# controller.net
KiCad netlist of a schematic drawn in EAGLE
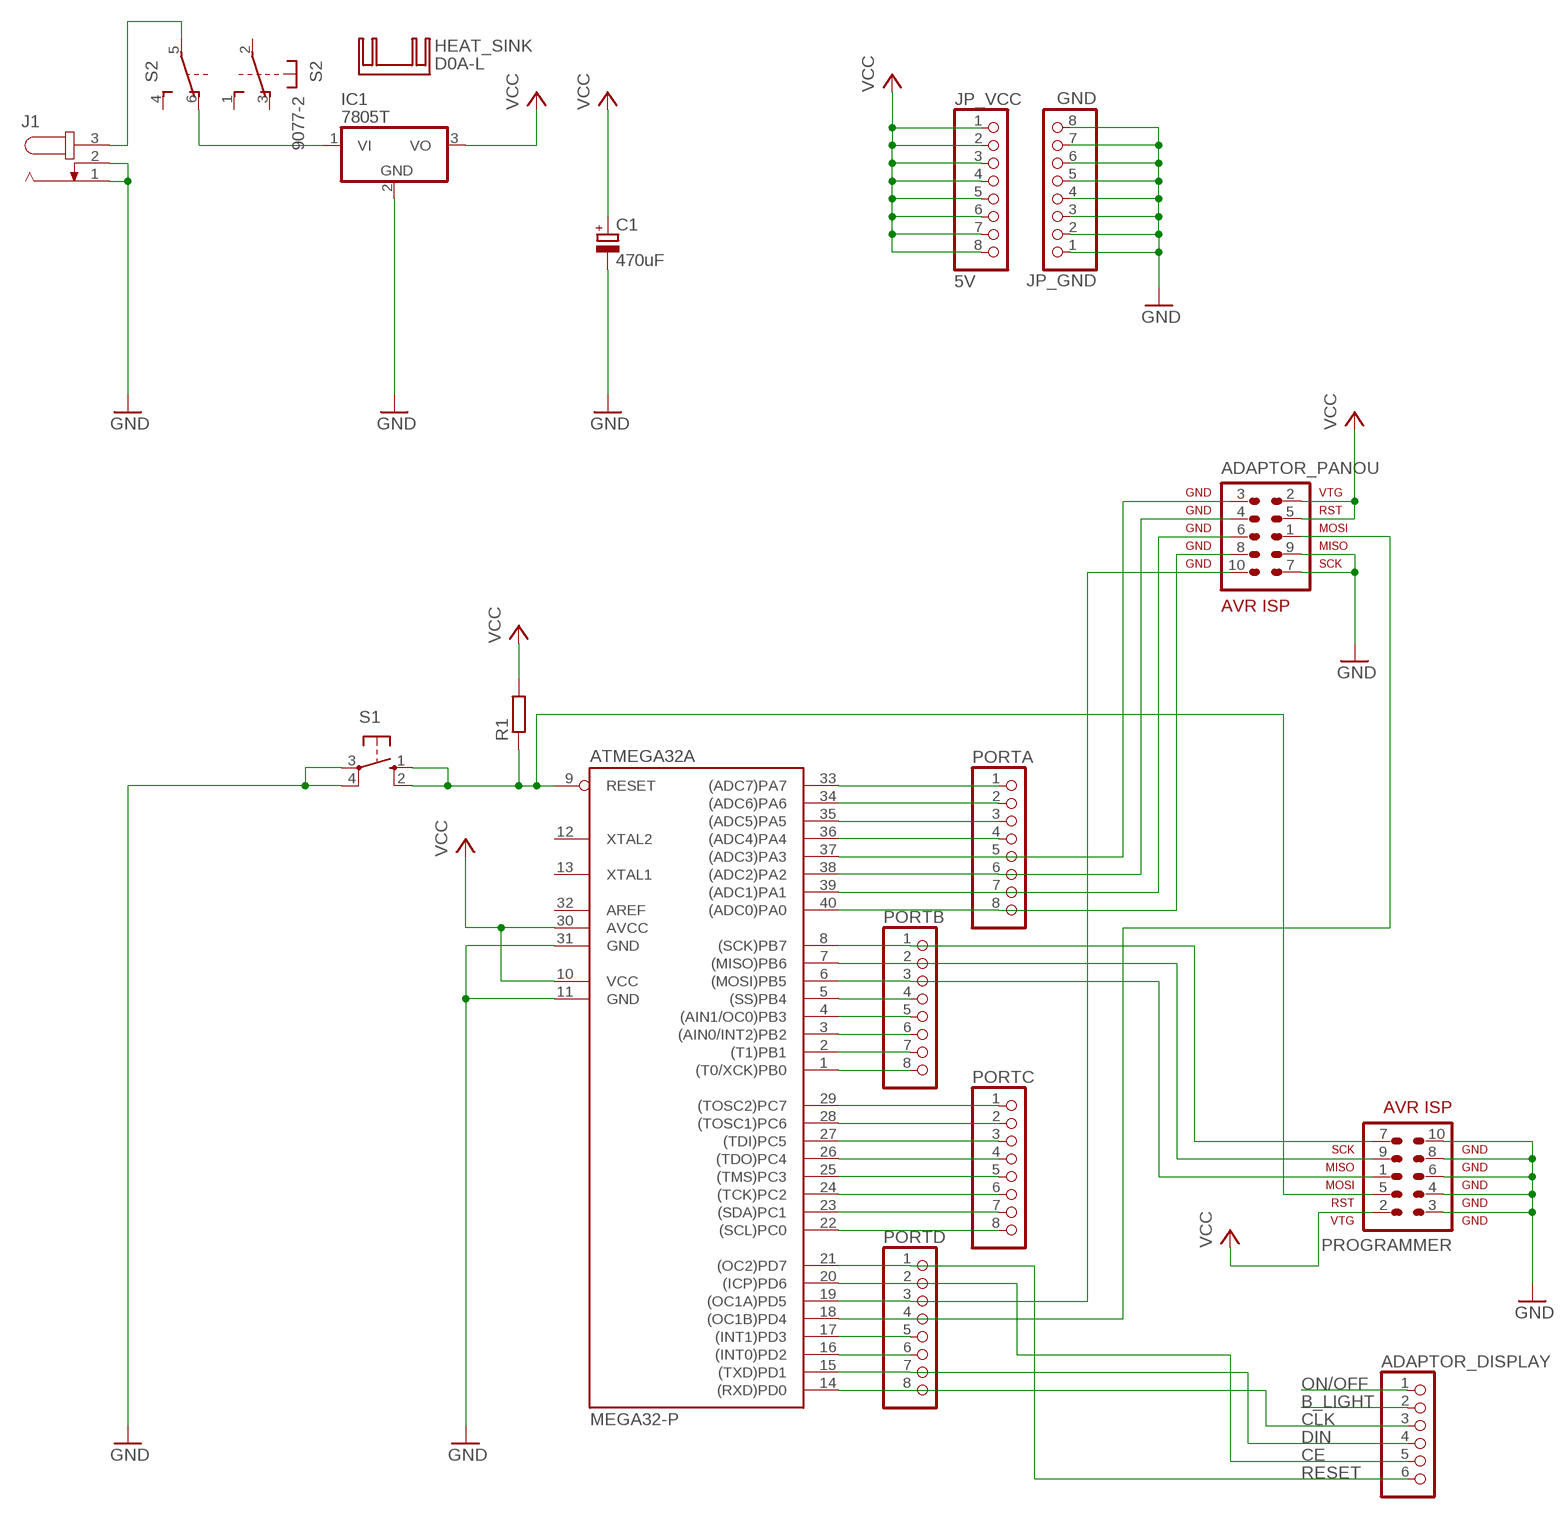
[diagram p0: schematic, sheet 1]

(export (version "E")
  (design (tool "Eeschema 10.0.6"))
  (components
    (comp (ref "ADAPTOR_DISPLAY")
      (value "PINHD-1X6")
      (footprint "eagle-import:1X06")
      (libsource (lib "eagle-import") (part "PINHD-1X6"))
    )
    (comp (ref "ADAPTOR_PANOU")
      (value "AVR-ISP-10")
      (footprint "eagle-import:AVR-ISP-10")
      (libsource (lib "eagle-import") (part "AVR-ISP-10"))
    )
    (comp (ref "ATMEGA32A")
      (value "MEGA32-P")
      (footprint "eagle-import:DIL40")
      (fields (field (name "MPN") "ATMEGA32-16PU"))
      (libsource (lib "eagle-import") (part "MEGA32-P"))
    )
    (comp (ref "C1")
      (value "470uF")
      (footprint "eagle-import:E3,5-8")
      (libsource (lib "eagle-import") (part "CPOL-EUE3.5-8"))
    )
    (comp (ref "HEAT_SINK")
      (value "D0A-L")
      (footprint "eagle-import:D02A-L")
      (libsource (lib "eagle-import") (part "D0A-L"))
    )
    (comp (ref "IC1")
      (value "7805T")
      (footprint "eagle-import:TO220H")
      (libsource (lib "eagle-import") (part "78T05"))
    )
    (comp (ref "J1")
      (value "JACK-PLUG0")
      (footprint "eagle-import:SPC4077")
      (libsource (lib "eagle-import") (part "JACK-PLUG0"))
    )
    (comp (ref "JP_GND")
      (value "GND")
      (footprint "eagle-import:1X08")
      (libsource (lib "eagle-import") (part "PINHD-1X8"))
    )
    (comp (ref "JP_VCC")
      (value "5V")
      (footprint "eagle-import:1X08")
      (libsource (lib "eagle-import") (part "PINHD-1X8"))
    )
    (comp (ref "PORTA")
      (value "PINHD-1X8")
      (footprint "eagle-import:1X08")
      (libsource (lib "eagle-import") (part "PINHD-1X8"))
    )
    (comp (ref "PORTB")
      (value "PINHD-1X8")
      (footprint "eagle-import:1X08")
      (libsource (lib "eagle-import") (part "PINHD-1X8"))
    )
    (comp (ref "PORTC")
      (value "PINHD-1X8")
      (footprint "eagle-import:1X08")
      (libsource (lib "eagle-import") (part "PINHD-1X8"))
    )
    (comp (ref "PORTD")
      (value "PINHD-1X8")
      (footprint "eagle-import:1X08")
      (libsource (lib "eagle-import") (part "PINHD-1X8"))
    )
    (comp (ref "PROGRAMMER")
      (value "AVR-ISP-10")
      (footprint "eagle-import:AVR-ISP-10")
      (libsource (lib "eagle-import") (part "AVR-ISP-10"))
    )
    (comp (ref "R1")
      (value "R-EU_0207/10")
      (footprint "eagle-import:0207_10")
      (libsource (lib "eagle-import") (part "R-EU_0207/10"))
    )
    (comp (ref "S1")
      (value "10-XX")
      (footprint "eagle-import:B3F-10XX")
      (fields (field (name "MPN") "B3F-1000"))
      (libsource (lib "eagle-import") (part "10-XX"))
    )
    (comp (ref "S2")
      (value "9077-2")
      (footprint "eagle-import:9077-2")
      (libsource (lib "eagle-import") (part "9077-2"))
    )
  )
  (nets
    (net (code "1") (name "/B_LIGHT") (class "Default")
      (node (ref "ADAPTOR_DISPLAY") (pin "2") (pinfunction "2_2") (pintype "passive"))
    )
    (net (code "2") (name "/CE") (class "Default")
      (node (ref "ADAPTOR_DISPLAY") (pin "5") (pinfunction "5_5") (pintype "passive"))
      (node (ref "ATMEGA32A") (pin "20") (pinfunction "(ICP)PD6_20") (pintype "bidirectional"))
      (node (ref "PORTD") (pin "2") (pinfunction "2_2") (pintype "passive"))
    )
    (net (code "3") (name "/CLK") (class "Default")
      (node (ref "ADAPTOR_DISPLAY") (pin "3") (pinfunction "3_3") (pintype "passive"))
      (node (ref "ATMEGA32A") (pin "14") (pinfunction "(RXD)PD0_14") (pintype "bidirectional"))
      (node (ref "PORTD") (pin "8") (pinfunction "8_8") (pintype "passive"))
    )
    (net (code "4") (name "/DIN") (class "Default")
      (node (ref "ADAPTOR_DISPLAY") (pin "4") (pinfunction "4_4") (pintype "passive"))
      (node (ref "ATMEGA32A") (pin "15") (pinfunction "(TXD)PD1_15") (pintype "bidirectional"))
      (node (ref "PORTD") (pin "7") (pinfunction "7_7") (pintype "passive"))
    )
    (net (code "5") (name "/ON{slash}OFF") (class "Default")
      (node (ref "ADAPTOR_DISPLAY") (pin "1") (pinfunction "1_1") (pintype "passive"))
    )
    (net (code "6") (name "/RESET") (class "Default")
      (node (ref "ADAPTOR_DISPLAY") (pin "6") (pinfunction "6_6") (pintype "passive"))
      (node (ref "ATMEGA32A") (pin "21") (pinfunction "(OC2)PD7_21") (pintype "bidirectional"))
      (node (ref "PORTD") (pin "1") (pinfunction "1_1") (pintype "passive"))
    )
    (net (code "7") (name "GND") (class "Default")
      (node (ref "ADAPTOR_PANOU") (pin "7") (pinfunction "7_7") (pintype "passive"))
      (node (ref "ADAPTOR_PANOU") (pin "9") (pinfunction "9_9") (pintype "passive"))
      (node (ref "ATMEGA32A") (pin "11") (pinfunction "GND_11") (pintype "power_in"))
      (node (ref "ATMEGA32A") (pin "31") (pinfunction "GND_31") (pintype "power_in"))
      (node (ref "C1") (pin "-") (pinfunction "-_-") (pintype "passive"))
      (node (ref "IC1") (pin "2") (pinfunction "GND_2") (pintype "passive"))
      (node (ref "J1") (pin "1") (pinfunction "1_1") (pintype "passive"))
      (node (ref "J1") (pin "2") (pinfunction "2_2") (pintype "passive"))
      (node (ref "JP_GND") (pin "1") (pinfunction "1_1") (pintype "passive"))
      (node (ref "JP_GND") (pin "2") (pinfunction "2_2") (pintype "passive"))
      (node (ref "JP_GND") (pin "3") (pinfunction "3_3") (pintype "passive"))
      (node (ref "JP_GND") (pin "4") (pinfunction "4_4") (pintype "passive"))
      (node (ref "JP_GND") (pin "5") (pinfunction "5_5") (pintype "passive"))
      (node (ref "JP_GND") (pin "6") (pinfunction "6_6") (pintype "passive"))
      (node (ref "JP_GND") (pin "7") (pinfunction "7_7") (pintype "passive"))
      (node (ref "JP_GND") (pin "8") (pinfunction "8_8") (pintype "passive"))
      (node (ref "PROGRAMMER") (pin "10") (pinfunction "10_10") (pintype "passive"))
      (node (ref "PROGRAMMER") (pin "3") (pinfunction "3_3") (pintype "passive"))
      (node (ref "PROGRAMMER") (pin "4") (pinfunction "4_4") (pintype "passive"))
      (node (ref "PROGRAMMER") (pin "6") (pinfunction "6_6") (pintype "passive"))
      (node (ref "PROGRAMMER") (pin "8") (pinfunction "8_8") (pintype "passive"))
      (node (ref "S1") (pin "3") (pinfunction "P_3") (pintype "passive"))
      (node (ref "S1") (pin "4") (pinfunction "P1_4") (pintype "passive"))
    )
    (net (code "8") (name "Net-(ATMEGA32A-(ADC0)PA0)") (class "Default")
      (node (ref "ADAPTOR_PANOU") (pin "8") (pinfunction "8_8") (pintype "passive"))
      (node (ref "ATMEGA32A") (pin "40") (pinfunction "(ADC0)PA0_40") (pintype "bidirectional"))
      (node (ref "PORTA") (pin "8") (pinfunction "8_8") (pintype "passive"))
    )
    (net (code "9") (name "Net-(ATMEGA32A-(ADC1)PA1)") (class "Default")
      (node (ref "ADAPTOR_PANOU") (pin "6") (pinfunction "6_6") (pintype "passive"))
      (node (ref "ATMEGA32A") (pin "39") (pinfunction "(ADC1)PA1_39") (pintype "bidirectional"))
      (node (ref "PORTA") (pin "7") (pinfunction "7_7") (pintype "passive"))
    )
    (net (code "10") (name "Net-(ATMEGA32A-(ADC2)PA2)") (class "Default")
      (node (ref "ADAPTOR_PANOU") (pin "4") (pinfunction "4_4") (pintype "passive"))
      (node (ref "ATMEGA32A") (pin "38") (pinfunction "(ADC2)PA2_38") (pintype "bidirectional"))
      (node (ref "PORTA") (pin "6") (pinfunction "6_6") (pintype "passive"))
    )
    (net (code "11") (name "Net-(ATMEGA32A-(ADC3)PA3)") (class "Default")
      (node (ref "ADAPTOR_PANOU") (pin "3") (pinfunction "3_3") (pintype "passive"))
      (node (ref "ATMEGA32A") (pin "37") (pinfunction "(ADC3)PA3_37") (pintype "bidirectional"))
      (node (ref "PORTA") (pin "5") (pinfunction "5_5") (pintype "passive"))
    )
    (net (code "12") (name "Net-(ATMEGA32A-(ADC4)PA4)") (class "Default")
      (node (ref "ATMEGA32A") (pin "36") (pinfunction "(ADC4)PA4_36") (pintype "bidirectional"))
      (node (ref "PORTA") (pin "4") (pinfunction "4_4") (pintype "passive"))
    )
    (net (code "13") (name "Net-(ATMEGA32A-(ADC5)PA5)") (class "Default")
      (node (ref "ATMEGA32A") (pin "35") (pinfunction "(ADC5)PA5_35") (pintype "bidirectional"))
      (node (ref "PORTA") (pin "3") (pinfunction "3_3") (pintype "passive"))
    )
    (net (code "14") (name "Net-(ATMEGA32A-(ADC6)PA6)") (class "Default")
      (node (ref "ATMEGA32A") (pin "34") (pinfunction "(ADC6)PA6_34") (pintype "bidirectional"))
      (node (ref "PORTA") (pin "2") (pinfunction "2_2") (pintype "passive"))
    )
    (net (code "15") (name "Net-(ATMEGA32A-(ADC7)PA7)") (class "Default")
      (node (ref "ATMEGA32A") (pin "33") (pinfunction "(ADC7)PA7_33") (pintype "bidirectional"))
      (node (ref "PORTA") (pin "1") (pinfunction "1_1") (pintype "passive"))
    )
    (net (code "16") (name "Net-(ATMEGA32A-(AIN0{slash}INT2)PB2)") (class "Default")
      (node (ref "ATMEGA32A") (pin "3") (pinfunction "(AIN0/INT2)PB2_3") (pintype "bidirectional"))
      (node (ref "PORTB") (pin "6") (pinfunction "6_6") (pintype "passive"))
    )
    (net (code "17") (name "Net-(ATMEGA32A-(AIN1{slash}OC0)PB3)") (class "Default")
      (node (ref "ATMEGA32A") (pin "4") (pinfunction "(AIN1/OC0)PB3_4") (pintype "bidirectional"))
      (node (ref "PORTB") (pin "5") (pinfunction "5_5") (pintype "passive"))
    )
    (net (code "18") (name "Net-(ATMEGA32A-(INT0)PD2)") (class "Default")
      (node (ref "ATMEGA32A") (pin "16") (pinfunction "(INT0)PD2_16") (pintype "bidirectional"))
      (node (ref "PORTD") (pin "6") (pinfunction "6_6") (pintype "passive"))
    )
    (net (code "19") (name "Net-(ATMEGA32A-(INT1)PD3)") (class "Default")
      (node (ref "ATMEGA32A") (pin "17") (pinfunction "(INT1)PD3_17") (pintype "bidirectional"))
      (node (ref "PORTD") (pin "5") (pinfunction "5_5") (pintype "passive"))
    )
    (net (code "20") (name "Net-(ATMEGA32A-(MISO)PB6)") (class "Default")
      (node (ref "ATMEGA32A") (pin "7") (pinfunction "(MISO)PB6_7") (pintype "bidirectional"))
      (node (ref "PORTB") (pin "2") (pinfunction "2_2") (pintype "passive"))
      (node (ref "PROGRAMMER") (pin "9") (pinfunction "9_9") (pintype "passive"))
    )
    (net (code "21") (name "Net-(ATMEGA32A-(MOSI)PB5)") (class "Default")
      (node (ref "ATMEGA32A") (pin "6") (pinfunction "(MOSI)PB5_6") (pintype "bidirectional"))
      (node (ref "PORTB") (pin "3") (pinfunction "3_3") (pintype "passive"))
      (node (ref "PROGRAMMER") (pin "1") (pinfunction "1_1") (pintype "passive"))
    )
    (net (code "22") (name "Net-(ATMEGA32A-(OC1A)PD5)") (class "Default")
      (node (ref "ADAPTOR_PANOU") (pin "10") (pinfunction "10_10") (pintype "passive"))
      (node (ref "ATMEGA32A") (pin "19") (pinfunction "(OC1A)PD5_19") (pintype "bidirectional"))
      (node (ref "PORTD") (pin "3") (pinfunction "3_3") (pintype "passive"))
    )
    (net (code "23") (name "Net-(ATMEGA32A-(OC1B)PD4)") (class "Default")
      (node (ref "ADAPTOR_PANOU") (pin "1") (pinfunction "1_1") (pintype "passive"))
      (node (ref "ATMEGA32A") (pin "18") (pinfunction "(OC1B)PD4_18") (pintype "bidirectional"))
      (node (ref "PORTD") (pin "4") (pinfunction "4_4") (pintype "passive"))
    )
    (net (code "24") (name "Net-(ATMEGA32A-(SCK)PB7)") (class "Default")
      (node (ref "ATMEGA32A") (pin "8") (pinfunction "(SCK)PB7_8") (pintype "bidirectional"))
      (node (ref "PORTB") (pin "1") (pinfunction "1_1") (pintype "passive"))
      (node (ref "PROGRAMMER") (pin "7") (pinfunction "7_7") (pintype "passive"))
    )
    (net (code "25") (name "Net-(ATMEGA32A-(SCL)PC0)") (class "Default")
      (node (ref "ATMEGA32A") (pin "22") (pinfunction "(SCL)PC0_22") (pintype "bidirectional"))
      (node (ref "PORTC") (pin "8") (pinfunction "8_8") (pintype "passive"))
    )
    (net (code "26") (name "Net-(ATMEGA32A-(SDA)PC1)") (class "Default")
      (node (ref "ATMEGA32A") (pin "23") (pinfunction "(SDA)PC1_23") (pintype "bidirectional"))
      (node (ref "PORTC") (pin "7") (pinfunction "7_7") (pintype "passive"))
    )
    (net (code "27") (name "Net-(ATMEGA32A-(SS)PB4)") (class "Default")
      (node (ref "ATMEGA32A") (pin "5") (pinfunction "(SS)PB4_5") (pintype "bidirectional"))
      (node (ref "PORTB") (pin "4") (pinfunction "4_4") (pintype "passive"))
    )
    (net (code "28") (name "Net-(ATMEGA32A-(T0{slash}XCK)PB0)") (class "Default")
      (node (ref "ATMEGA32A") (pin "1") (pinfunction "(T0/XCK)PB0_1") (pintype "bidirectional"))
      (node (ref "PORTB") (pin "8") (pinfunction "8_8") (pintype "passive"))
    )
    (net (code "29") (name "Net-(ATMEGA32A-(T1)PB1)") (class "Default")
      (node (ref "ATMEGA32A") (pin "2") (pinfunction "(T1)PB1_2") (pintype "bidirectional"))
      (node (ref "PORTB") (pin "7") (pinfunction "7_7") (pintype "passive"))
    )
    (net (code "30") (name "Net-(ATMEGA32A-(TCK)PC2)") (class "Default")
      (node (ref "ATMEGA32A") (pin "24") (pinfunction "(TCK)PC2_24") (pintype "bidirectional"))
      (node (ref "PORTC") (pin "6") (pinfunction "6_6") (pintype "passive"))
    )
    (net (code "31") (name "Net-(ATMEGA32A-(TDI)PC5)") (class "Default")
      (node (ref "ATMEGA32A") (pin "27") (pinfunction "(TDI)PC5_27") (pintype "bidirectional"))
      (node (ref "PORTC") (pin "3") (pinfunction "3_3") (pintype "passive"))
    )
    (net (code "32") (name "Net-(ATMEGA32A-(TDO)PC4)") (class "Default")
      (node (ref "ATMEGA32A") (pin "26") (pinfunction "(TDO)PC4_26") (pintype "bidirectional"))
      (node (ref "PORTC") (pin "4") (pinfunction "4_4") (pintype "passive"))
    )
    (net (code "33") (name "Net-(ATMEGA32A-(TMS)PC3)") (class "Default")
      (node (ref "ATMEGA32A") (pin "25") (pinfunction "(TMS)PC3_25") (pintype "bidirectional"))
      (node (ref "PORTC") (pin "5") (pinfunction "5_5") (pintype "passive"))
    )
    (net (code "34") (name "Net-(ATMEGA32A-(TOSC1)PC6)") (class "Default")
      (node (ref "ATMEGA32A") (pin "28") (pinfunction "(TOSC1)PC6_28") (pintype "bidirectional"))
      (node (ref "PORTC") (pin "2") (pinfunction "2_2") (pintype "passive"))
    )
    (net (code "35") (name "Net-(ATMEGA32A-(TOSC2)PC7)") (class "Default")
      (node (ref "ATMEGA32A") (pin "29") (pinfunction "(TOSC2)PC7_29") (pintype "bidirectional"))
      (node (ref "PORTC") (pin "1") (pinfunction "1_1") (pintype "passive"))
    )
    (net (code "36") (name "Net-(ATMEGA32A-RESET)") (class "Default")
      (node (ref "ATMEGA32A") (pin "9") (pinfunction "RESET_9") (pintype "input"))
      (node (ref "PROGRAMMER") (pin "5") (pinfunction "5_5") (pintype "passive"))
      (node (ref "R1") (pin "1") (pinfunction "1_1") (pintype "passive"))
      (node (ref "S1") (pin "1") (pinfunction "S_1") (pintype "passive"))
      (node (ref "S1") (pin "2") (pinfunction "S1_2") (pintype "passive"))
    )
    (net (code "37") (name "Net-(IC1-VI)") (class "Default")
      (node (ref "IC1") (pin "1") (pinfunction "VI_1") (pintype "input"))
      (node (ref "S2") (pin "6") (pinfunction "O_6") (pintype "passive"))
    )
    (net (code "38") (name "Net-(S2B-P)") (class "Default")
      (node (ref "J1") (pin "3") (pinfunction "3_3") (pintype "passive"))
      (node (ref "S2") (pin "5") (pinfunction "P_5") (pintype "passive"))
    )
    (net (code "39") (name "VCC") (class "Default")
      (node (ref "ADAPTOR_PANOU") (pin "2") (pinfunction "2_2") (pintype "passive"))
      (node (ref "ADAPTOR_PANOU") (pin "5") (pinfunction "5_5") (pintype "passive"))
      (node (ref "ATMEGA32A") (pin "10") (pinfunction "VCC_10") (pintype "power_in"))
      (node (ref "ATMEGA32A") (pin "30") (pinfunction "AVCC_30") (pintype "power_in"))
      (node (ref "C1") (pin "+") (pinfunction "+_+") (pintype "passive"))
      (node (ref "IC1") (pin "3") (pinfunction "VO_3") (pintype "passive"))
      (node (ref "JP_VCC") (pin "1") (pinfunction "1_1") (pintype "passive"))
      (node (ref "JP_VCC") (pin "2") (pinfunction "2_2") (pintype "passive"))
      (node (ref "JP_VCC") (pin "3") (pinfunction "3_3") (pintype "passive"))
      (node (ref "JP_VCC") (pin "4") (pinfunction "4_4") (pintype "passive"))
      (node (ref "JP_VCC") (pin "5") (pinfunction "5_5") (pintype "passive"))
      (node (ref "JP_VCC") (pin "6") (pinfunction "6_6") (pintype "passive"))
      (node (ref "JP_VCC") (pin "7") (pinfunction "7_7") (pintype "passive"))
      (node (ref "JP_VCC") (pin "8") (pinfunction "8_8") (pintype "passive"))
      (node (ref "PROGRAMMER") (pin "2") (pinfunction "2_2") (pintype "passive"))
      (node (ref "R1") (pin "2") (pinfunction "2_2") (pintype "passive"))
    )
    (net (code "40") (name "unconnected-(ATMEGA32A-AREF-Pad32)") (class "Default")
      (node (ref "ATMEGA32A") (pin "32") (pinfunction "AREF_32") (pintype "passive"))
    )
    (net (code "41") (name "unconnected-(ATMEGA32A-XTAL1-Pad13)") (class "Default")
      (node (ref "ATMEGA32A") (pin "13") (pinfunction "XTAL1_13") (pintype "bidirectional"))
    )
    (net (code "42") (name "unconnected-(ATMEGA32A-XTAL2-Pad12)") (class "Default")
      (node (ref "ATMEGA32A") (pin "12") (pinfunction "XTAL2_12") (pintype "bidirectional"))
    )
    (net (code "43") (name "unconnected-(S2A-O-Pad3)") (class "Default")
      (node (ref "S2") (pin "3") (pinfunction "O_3") (pintype "passive"))
    )
    (net (code "44") (name "unconnected-(S2A-P-Pad2)") (class "Default")
      (node (ref "S2") (pin "2") (pinfunction "P_2") (pintype "passive"))
    )
    (net (code "45") (name "unconnected-(S2A-S-Pad1)") (class "Default")
      (node (ref "S2") (pin "1") (pinfunction "S_1") (pintype "passive"))
    )
    (net (code "46") (name "unconnected-(S2B-S-Pad4)") (class "Default")
      (node (ref "S2") (pin "4") (pinfunction "S_4") (pintype "passive"))
    )
  )
)
